# 1V8_Arc_Welder.net
KiCad netlist of a schematic drawn in EAGLE
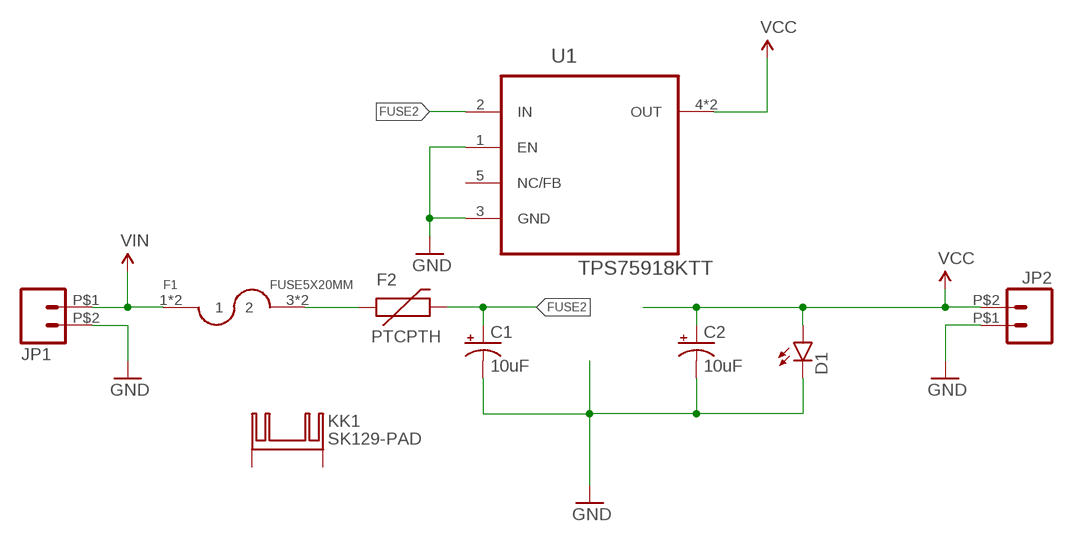
[diagram p0: schematic, sheet 1]

(export (version "E")
  (design (tool "Eeschema 10.0.6"))
  (components
    (comp (ref "C1")
      (value "10uF")
      (footprint "eagle-import:E2-5")
      (libsource (lib "eagle-import") (part "CPOL-USE2-5"))
    )
    (comp (ref "C2")
      (value "10uF")
      (footprint "eagle-import:E2-5")
      (libsource (lib "eagle-import") (part "CPOL-USE2-5"))
    )
    (comp (ref "D1")
      (value "LED5MM")
      (footprint "eagle-import:LED5MM")
      (libsource (lib "eagle-import") (part "LED5MM"))
    )
    (comp (ref "F1")
      (value "FUSE5X20MM")
      (footprint "eagle-import:FUSE_1A3399")
      (libsource (lib "eagle-import") (part "FUSE5X20MM"))
    )
    (comp (ref "F2")
      (value "PTCPTH")
      (footprint "eagle-import:PTC")
      (libsource (lib "eagle-import") (part "PTCPTH"))
    )
    (comp (ref "JP1")
      (value "M02TE-282834-2")
      (footprint "eagle-import:1X02_282834-2")
      (libsource (lib "eagle-import") (part "M02TE-282834-2"))
    )
    (comp (ref "JP2")
      (value "M02TE-282834-2")
      (footprint "eagle-import:1X02_282834-2")
      (libsource (lib "eagle-import") (part "M02TE-282834-2"))
    )
    (comp (ref "KK1")
      (value "SK129-PAD")
      (footprint "eagle-import:SK129")
      (libsource (lib "eagle-import") (part "SK129-PAD"))
    )
    (comp (ref "U1")
      (value "TPS75918KTT")
      (footprint "eagle-import:TO263-5")
      (libsource (lib "eagle-import") (part "TPS75918KTT"))
    )
  )
  (nets
    (net (code "1") (name "FUSE2") (class "Default")
      (node (ref "C1") (pin "+") (pinfunction "+_+") (pintype "passive"))
      (node (ref "F2") (pin "P$2") (pinfunction "2_P$2") (pintype "bidirectional"))
      (node (ref "U1") (pin "2") (pinfunction "IN_2") (pintype "power_in"))
    )
    (net (code "2") (name "GND") (class "Default")
      (node (ref "C1") (pin "-") (pinfunction "-_-") (pintype "passive"))
      (node (ref "C2") (pin "-") (pinfunction "-_-") (pintype "passive"))
      (node (ref "D1") (pin "K") (pinfunction "C_K") (pintype "passive"))
      (node (ref "JP1") (pin "P$2") (pinfunction "2_P$2") (pintype "passive"))
      (node (ref "JP2") (pin "P$1") (pinfunction "1_P$1") (pintype "passive"))
      (node (ref "U1") (pin "1") (pinfunction "EN_1") (pintype "input"))
      (node (ref "U1") (pin "3") (pinfunction "GND_3") (pintype "passive"))
    )
    (net (code "3") (name "Net-(F2-1)") (class "Default")
      (node (ref "F1") (pin "3") (pinfunction "2_3") (pintype "bidirectional"))
      (node (ref "F1") (pin "4") (pinfunction "2_4") (pintype "bidirectional"))
      (node (ref "F2") (pin "P$1") (pinfunction "1_P$1") (pintype "bidirectional"))
    )
    (net (code "4") (name "VCC") (class "Default")
      (node (ref "C2") (pin "+") (pinfunction "+_+") (pintype "passive"))
      (node (ref "D1") (pin "A") (pinfunction "A_A") (pintype "passive"))
      (node (ref "JP2") (pin "P$2") (pinfunction "2_P$2") (pintype "passive"))
      (node (ref "U1") (pin "4") (pinfunction "OUT_4") (pintype "output"))
      (node (ref "U1") (pin "6") (pinfunction "OUT_6") (pintype "output"))
    )
    (net (code "5") (name "VIN") (class "Default")
      (node (ref "F1") (pin "1") (pinfunction "1_1") (pintype "bidirectional"))
      (node (ref "F1") (pin "2") (pinfunction "1_2") (pintype "bidirectional"))
      (node (ref "JP1") (pin "P$1") (pinfunction "1_P$1") (pintype "passive"))
    )
    (net (code "6") (name "unconnected-(KK1-K-PadA2,5)") (class "Default")
      (node (ref "KK1") (pin "A2,5") (pinfunction "K_A2,5") (pintype "passive"))
    )
    (net (code "7") (name "unconnected-(KK1-K-PadB2,5)") (class "Default")
      (node (ref "KK1") (pin "B2,5") (pinfunction "K_B2,5") (pintype "passive"))
    )
    (net (code "8") (name "unconnected-(U1-NC{slash}FB-Pad5)") (class "Default")
      (node (ref "U1") (pin "5") (pinfunction "NC/FB_5") (pintype "no_connect"))
    )
  )
)
